# bai1.net
KiCad netlist of a schematic drawn in Altium Designer
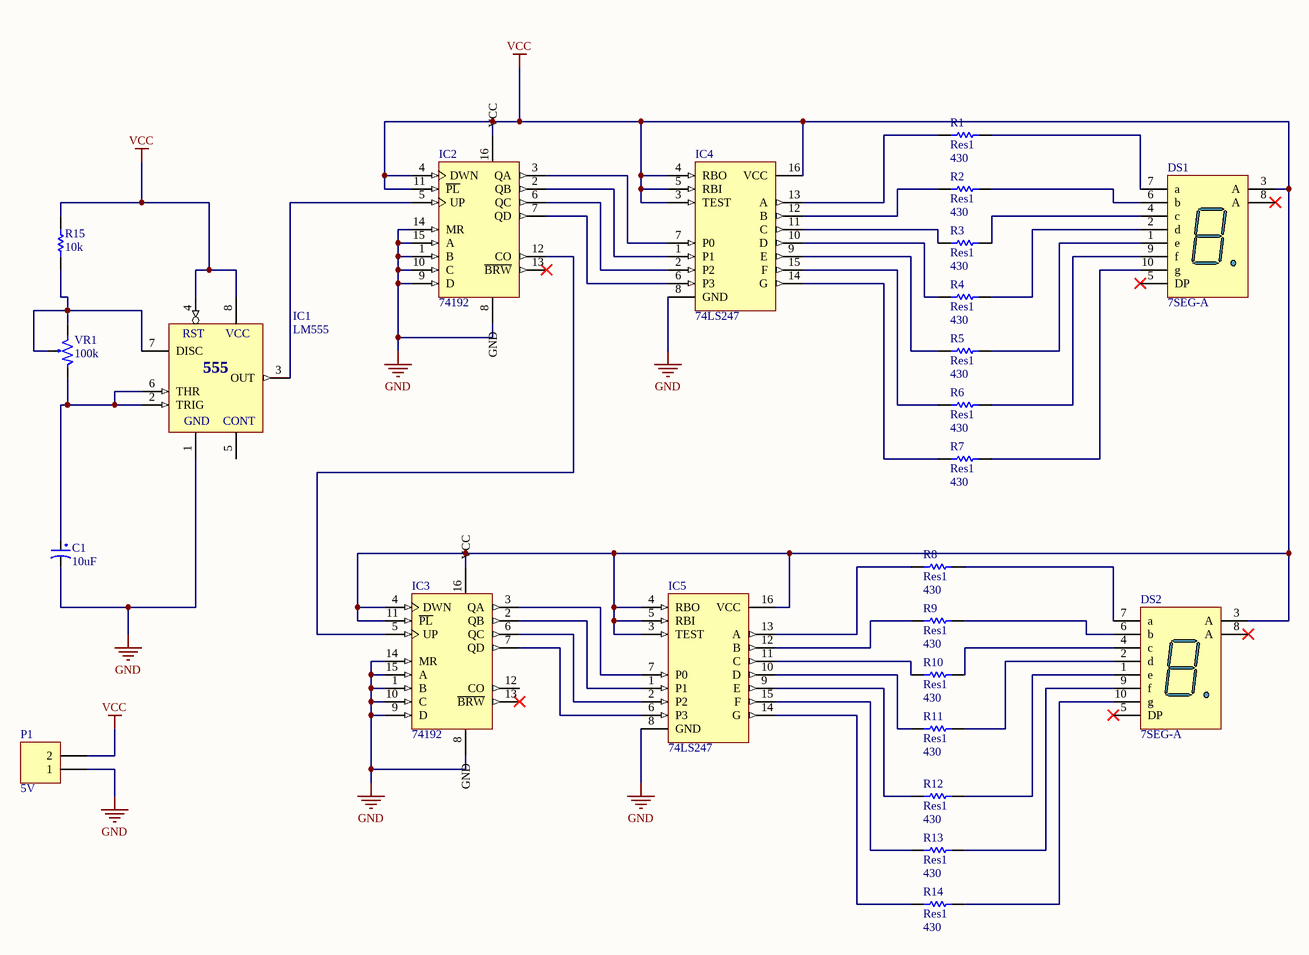
[diagram p0: bai1.SchDoc]

(export (version "E")
  (design (tool "Eeschema 10.0.6"))
  (components
    (comp (ref "C1")
      (value "10uF")
      (footprint "CP1/2")
      (description "Cap P  0,1uF < 22uF , 16 - 50V")
      (libsource (lib "syhaunguyen") (part "CP1"))
    )
    (comp (ref "DS1")
      (value "7SEG-A")
      (footprint "LED7SEG")
      (description "14.2 mm General Purpose Blue 7-Segment Display: CA, RH DP, Gray Surface")
      (fields (field (name "PUBLISHER") "Altium Limited"))
      (libsource (lib "Cty1") (part "LED7SEG-A"))
    )
    (comp (ref "DS2")
      (value "7SEG-A")
      (footprint "LED7SEG")
      (description "14.2 mm General Purpose Blue 7-Segment Display: CA, RH DP, Gray Surface")
      (fields (field (name "PUBLISHER") "Altium Limited"))
      (libsource (lib "Cty1") (part "LED7SEG-A"))
    )
    (comp (ref "IC1")
      (value "LM555")
      (footprint "VioletofSun:DIP8/W0.3")
      (description "Timer")
      (libsource (lib "VioletofSun") (part "LM555"))
    )
    (comp (ref "IC2")
      (value "74192")
      (footprint "DIP16/W0.3")
      (description "Synchronous 4-Bit Up/Down Counter")
      (fields (field (name "COPYRIGHT BY") "VanDungEvn@Gmail.com"))
      (libsource (lib "VioletofSun") (part "74193"))
    )
    (comp (ref "IC3")
      (value "74192")
      (footprint "DIP16/W0.3")
      (description "Synchronous 4-Bit Up/Down Counter")
      (fields (field (name "COPYRIGHT BY") "VanDungEvn@Gmail.com"))
      (libsource (lib "VioletofSun") (part "74193"))
    )
    (comp (ref "IC4")
      (value "74LS247")
      (footprint "DIP16")
      (fields (field (name "COPYRIGHT BY") "VanDungEvn@Gmail.com"))
      (libsource (lib "My Library") (part "74247"))
    )
    (comp (ref "IC5")
      (value "74LS247")
      (footprint "DIP16")
      (fields (field (name "COPYRIGHT BY") "VanDungEvn@Gmail.com"))
      (libsource (lib "My Library") (part "74247"))
    )
    (comp (ref "P1")
      (value "5V")
      (footprint "HDR1X2")
      (description "Header, 2-Pin")
      (fields (field (name "PUBLISHER") "Altium Limited"))
      (libsource (lib "Miscellaneous Connectors") (part "Header 2"))
    )
    (comp (ref "R1")
      (value "Res1")
      (footprint "AXIAL-0.3")
      (description "Resistor")
      (fields (field (name "ALTIUM_VALUE") "430") (field (name "PUBLISHER") "Altium Limited"))
      (libsource (lib "Miscellaneous Devices") (part "Res1"))
    )
    (comp (ref "R2")
      (value "Res1")
      (footprint "AXIAL-0.3")
      (description "Resistor")
      (fields (field (name "ALTIUM_VALUE") "430") (field (name "PUBLISHER") "Altium Limited"))
      (libsource (lib "Miscellaneous Devices") (part "Res1"))
    )
    (comp (ref "R3")
      (value "Res1")
      (footprint "AXIAL-0.3")
      (description "Resistor")
      (fields (field (name "ALTIUM_VALUE") "430") (field (name "PUBLISHER") "Altium Limited"))
      (libsource (lib "Miscellaneous Devices") (part "Res1"))
    )
    (comp (ref "R4")
      (value "Res1")
      (footprint "AXIAL-0.3")
      (description "Resistor")
      (fields (field (name "ALTIUM_VALUE") "430") (field (name "PUBLISHER") "Altium Limited"))
      (libsource (lib "Miscellaneous Devices") (part "Res1"))
    )
    (comp (ref "R5")
      (value "Res1")
      (footprint "AXIAL-0.3")
      (description "Resistor")
      (fields (field (name "ALTIUM_VALUE") "430") (field (name "PUBLISHER") "Altium Limited"))
      (libsource (lib "Miscellaneous Devices") (part "Res1"))
    )
    (comp (ref "R6")
      (value "Res1")
      (footprint "AXIAL-0.3")
      (description "Resistor")
      (fields (field (name "ALTIUM_VALUE") "430") (field (name "PUBLISHER") "Altium Limited"))
      (libsource (lib "Miscellaneous Devices") (part "Res1"))
    )
    (comp (ref "R7")
      (value "Res1")
      (footprint "AXIAL-0.3")
      (description "Resistor")
      (fields (field (name "ALTIUM_VALUE") "430") (field (name "PUBLISHER") "Altium Limited"))
      (libsource (lib "Miscellaneous Devices") (part "Res1"))
    )
    (comp (ref "R8")
      (value "Res1")
      (footprint "AXIAL-0.3")
      (description "Resistor")
      (fields (field (name "ALTIUM_VALUE") "430") (field (name "PUBLISHER") "Altium Limited"))
      (libsource (lib "Miscellaneous Devices") (part "Res1"))
    )
    (comp (ref "R9")
      (value "Res1")
      (footprint "AXIAL-0.3")
      (description "Resistor")
      (fields (field (name "ALTIUM_VALUE") "430") (field (name "PUBLISHER") "Altium Limited"))
      (libsource (lib "Miscellaneous Devices") (part "Res1"))
    )
    (comp (ref "R10")
      (value "Res1")
      (footprint "AXIAL-0.3")
      (description "Resistor")
      (fields (field (name "ALTIUM_VALUE") "430") (field (name "PUBLISHER") "Altium Limited"))
      (libsource (lib "Miscellaneous Devices") (part "Res1"))
    )
    (comp (ref "R11")
      (value "Res1")
      (footprint "AXIAL-0.3")
      (description "Resistor")
      (fields (field (name "ALTIUM_VALUE") "430") (field (name "PUBLISHER") "Altium Limited"))
      (libsource (lib "Miscellaneous Devices") (part "Res1"))
    )
    (comp (ref "R12")
      (value "Res1")
      (footprint "AXIAL-0.3")
      (description "Resistor")
      (fields (field (name "ALTIUM_VALUE") "430") (field (name "PUBLISHER") "Altium Limited"))
      (libsource (lib "Miscellaneous Devices") (part "Res1"))
    )
    (comp (ref "R13")
      (value "Res1")
      (footprint "AXIAL-0.3")
      (description "Resistor")
      (fields (field (name "ALTIUM_VALUE") "430") (field (name "PUBLISHER") "Altium Limited"))
      (libsource (lib "Miscellaneous Devices") (part "Res1"))
    )
    (comp (ref "R14")
      (value "Res1")
      (footprint "AXIAL-0.3")
      (description "Resistor")
      (fields (field (name "ALTIUM_VALUE") "430") (field (name "PUBLISHER") "Altium Limited"))
      (libsource (lib "Miscellaneous Devices") (part "Res1"))
    )
    (comp (ref "R15")
      (value "10k")
      (footprint "R1/4W")
      (description "Resistor")
      (fields
        (field (name "MANUFACTURER") "Generic Components")
        (field (name "Comment") "Res1")
        (field (name "PUBLISHER") "Altium Hobart Technology Centre")
      )
      (libsource (lib "thuvien3D") (part "Res1_1"))
    )
    (comp (ref "VR1")
      (value "100k")
      (footprint "VR")
      (description "Var Resistor")
      (libsource (lib "syhaunguyen") (part "VR1"))
    )
  )
  (nets
    (net (code "1") (name "GND") (class "Default")
      (node (ref "C1") (pin "2") (pinfunction "2_2") (pintype "passive"))
      (node (ref "IC1") (pin "1") (pinfunction "GND_1") (pintype "power_in"))
      (node (ref "IC2") (pin "1") (pinfunction "B_1") (pintype "input"))
      (node (ref "IC2") (pin "10") (pinfunction "C_10") (pintype "input"))
      (node (ref "IC2") (pin "14") (pinfunction "MR_14") (pintype "input"))
      (node (ref "IC2") (pin "15") (pinfunction "A_15") (pintype "input"))
      (node (ref "IC2") (pin "9") (pinfunction "D_9") (pintype "input"))
      (node (ref "IC3") (pin "1") (pinfunction "B_1") (pintype "input"))
      (node (ref "IC3") (pin "10") (pinfunction "C_10") (pintype "input"))
      (node (ref "IC3") (pin "14") (pinfunction "MR_14") (pintype "input"))
      (node (ref "IC3") (pin "15") (pinfunction "A_15") (pintype "input"))
      (node (ref "IC3") (pin "9") (pinfunction "D_9") (pintype "input"))
      (node (ref "IC4") (pin "8") (pinfunction "GND_8") (pintype "power_in"))
      (node (ref "IC5") (pin "8") (pinfunction "GND_8") (pintype "power_in"))
      (node (ref "P1") (pin "1") (pinfunction "1_1") (pintype "passive"))
    )
    (net (code "2") (name "Net-(DS1-a)") (class "Default")
      (node (ref "DS1") (pin "7") (pinfunction "a_7") (pintype "passive"))
      (node (ref "R1") (pin "2") (pinfunction "2_2") (pintype "passive"))
    )
    (net (code "3") (name "Net-(DS1-b)") (class "Default")
      (node (ref "DS1") (pin "6") (pinfunction "b_6") (pintype "passive"))
      (node (ref "R2") (pin "2") (pinfunction "2_2") (pintype "passive"))
    )
    (net (code "4") (name "Net-(DS1-c)") (class "Default")
      (node (ref "DS1") (pin "4") (pinfunction "c_4") (pintype "passive"))
      (node (ref "R3") (pin "2") (pinfunction "2_2") (pintype "passive"))
    )
    (net (code "5") (name "Net-(DS1-d)") (class "Default")
      (node (ref "DS1") (pin "2") (pinfunction "d_2") (pintype "passive"))
      (node (ref "R4") (pin "2") (pinfunction "2_2") (pintype "passive"))
    )
    (net (code "6") (name "Net-(DS1-e)") (class "Default")
      (node (ref "DS1") (pin "1") (pinfunction "e_1") (pintype "passive"))
      (node (ref "R5") (pin "2") (pinfunction "2_2") (pintype "passive"))
    )
    (net (code "7") (name "Net-(DS1-f)") (class "Default")
      (node (ref "DS1") (pin "9") (pinfunction "f_9") (pintype "passive"))
      (node (ref "R6") (pin "2") (pinfunction "2_2") (pintype "passive"))
    )
    (net (code "8") (name "Net-(DS1-g)") (class "Default")
      (node (ref "DS1") (pin "10") (pinfunction "g_10") (pintype "passive"))
      (node (ref "R7") (pin "2") (pinfunction "2_2") (pintype "passive"))
    )
    (net (code "9") (name "Net-(DS2-a)") (class "Default")
      (node (ref "DS2") (pin "7") (pinfunction "a_7") (pintype "passive"))
      (node (ref "R8") (pin "2") (pinfunction "2_2") (pintype "passive"))
    )
    (net (code "10") (name "Net-(DS2-b)") (class "Default")
      (node (ref "DS2") (pin "6") (pinfunction "b_6") (pintype "passive"))
      (node (ref "R9") (pin "2") (pinfunction "2_2") (pintype "passive"))
    )
    (net (code "11") (name "Net-(DS2-c)") (class "Default")
      (node (ref "DS2") (pin "4") (pinfunction "c_4") (pintype "passive"))
      (node (ref "R10") (pin "2") (pinfunction "2_2") (pintype "passive"))
    )
    (net (code "12") (name "Net-(DS2-d)") (class "Default")
      (node (ref "DS2") (pin "2") (pinfunction "d_2") (pintype "passive"))
      (node (ref "R11") (pin "2") (pinfunction "2_2") (pintype "passive"))
    )
    (net (code "13") (name "Net-(DS2-e)") (class "Default")
      (node (ref "DS2") (pin "1") (pinfunction "e_1") (pintype "passive"))
      (node (ref "R12") (pin "2") (pinfunction "2_2") (pintype "passive"))
    )
    (net (code "14") (name "Net-(DS2-f)") (class "Default")
      (node (ref "DS2") (pin "9") (pinfunction "f_9") (pintype "passive"))
      (node (ref "R13") (pin "2") (pinfunction "2_2") (pintype "passive"))
    )
    (net (code "15") (name "Net-(DS2-g)") (class "Default")
      (node (ref "DS2") (pin "10") (pinfunction "g_10") (pintype "passive"))
      (node (ref "R14") (pin "2") (pinfunction "2_2") (pintype "passive"))
    )
    (net (code "16") (name "Net-(IC1-DISC)") (class "Default")
      (node (ref "IC1") (pin "7") (pinfunction "DISC_7") (pintype "open_collector"))
      (node (ref "R15") (pin "1") (pinfunction "1_1") (pintype "passive"))
      (node (ref "VR1") (pin "2") (pinfunction "2_2") (pintype "passive"))
      (node (ref "VR1") (pin "3") (pinfunction "3_3") (pintype "passive"))
    )
    (net (code "17") (name "Net-(IC1-OUT)") (class "Default")
      (node (ref "IC1") (pin "3") (pinfunction "OUT_3") (pintype "output"))
      (node (ref "IC2") (pin "5") (pinfunction "UP_5") (pintype "input"))
    )
    (net (code "18") (name "Net-(IC1-THR)") (class "Default")
      (node (ref "C1") (pin "1") (pinfunction "1_1") (pintype "passive"))
      (node (ref "IC1") (pin "2") (pinfunction "TRIG_2") (pintype "input"))
      (node (ref "IC1") (pin "6") (pinfunction "THR_6") (pintype "input"))
      (node (ref "VR1") (pin "1") (pinfunction "1_1") (pintype "passive"))
    )
    (net (code "19") (name "Net-(IC2-CO)") (class "Default")
      (node (ref "IC2") (pin "12") (pinfunction "CO_12") (pintype "output"))
      (node (ref "IC3") (pin "5") (pinfunction "UP_5") (pintype "input"))
    )
    (net (code "20") (name "Net-(IC2-QA)") (class "Default")
      (node (ref "IC2") (pin "3") (pinfunction "QA_3") (pintype "output"))
      (node (ref "IC4") (pin "7") (pinfunction "P0_7") (pintype "input"))
    )
    (net (code "21") (name "Net-(IC2-QB)") (class "Default")
      (node (ref "IC2") (pin "2") (pinfunction "QB_2") (pintype "output"))
      (node (ref "IC4") (pin "1") (pinfunction "P1_1") (pintype "input"))
    )
    (net (code "22") (name "Net-(IC2-QC)") (class "Default")
      (node (ref "IC2") (pin "6") (pinfunction "QC_6") (pintype "output"))
      (node (ref "IC4") (pin "2") (pinfunction "P2_2") (pintype "input"))
    )
    (net (code "23") (name "Net-(IC2-QD)") (class "Default")
      (node (ref "IC2") (pin "7") (pinfunction "QD_7") (pintype "output"))
      (node (ref "IC4") (pin "6") (pinfunction "P3_6") (pintype "input"))
    )
    (net (code "24") (name "Net-(IC3-QA)") (class "Default")
      (node (ref "IC3") (pin "3") (pinfunction "QA_3") (pintype "output"))
      (node (ref "IC5") (pin "7") (pinfunction "P0_7") (pintype "input"))
    )
    (net (code "25") (name "Net-(IC3-QB)") (class "Default")
      (node (ref "IC3") (pin "2") (pinfunction "QB_2") (pintype "output"))
      (node (ref "IC5") (pin "1") (pinfunction "P1_1") (pintype "input"))
    )
    (net (code "26") (name "Net-(IC3-QC)") (class "Default")
      (node (ref "IC3") (pin "6") (pinfunction "QC_6") (pintype "output"))
      (node (ref "IC5") (pin "2") (pinfunction "P2_2") (pintype "input"))
    )
    (net (code "27") (name "Net-(IC3-QD)") (class "Default")
      (node (ref "IC3") (pin "7") (pinfunction "QD_7") (pintype "output"))
      (node (ref "IC5") (pin "6") (pinfunction "P3_6") (pintype "input"))
    )
    (net (code "28") (name "Net-(IC4-A)") (class "Default")
      (node (ref "IC4") (pin "13") (pinfunction "A_13") (pintype "output"))
      (node (ref "R1") (pin "1") (pinfunction "1_1") (pintype "passive"))
    )
    (net (code "29") (name "Net-(IC4-B)") (class "Default")
      (node (ref "IC4") (pin "12") (pinfunction "B_12") (pintype "output"))
      (node (ref "R2") (pin "1") (pinfunction "1_1") (pintype "passive"))
    )
    (net (code "30") (name "Net-(IC4-C)") (class "Default")
      (node (ref "IC4") (pin "11") (pinfunction "C_11") (pintype "output"))
      (node (ref "R3") (pin "1") (pinfunction "1_1") (pintype "passive"))
    )
    (net (code "31") (name "Net-(IC4-D)") (class "Default")
      (node (ref "IC4") (pin "10") (pinfunction "D_10") (pintype "output"))
      (node (ref "R4") (pin "1") (pinfunction "1_1") (pintype "passive"))
    )
    (net (code "32") (name "Net-(IC4-E)") (class "Default")
      (node (ref "IC4") (pin "9") (pinfunction "E_9") (pintype "output"))
      (node (ref "R5") (pin "1") (pinfunction "1_1") (pintype "passive"))
    )
    (net (code "33") (name "Net-(IC4-F)") (class "Default")
      (node (ref "IC4") (pin "15") (pinfunction "F_15") (pintype "output"))
      (node (ref "R6") (pin "1") (pinfunction "1_1") (pintype "passive"))
    )
    (net (code "34") (name "Net-(IC4-G)") (class "Default")
      (node (ref "IC4") (pin "14") (pinfunction "G_14") (pintype "output"))
      (node (ref "R7") (pin "1") (pinfunction "1_1") (pintype "passive"))
    )
    (net (code "35") (name "Net-(IC5-A)") (class "Default")
      (node (ref "IC5") (pin "13") (pinfunction "A_13") (pintype "output"))
      (node (ref "R8") (pin "1") (pinfunction "1_1") (pintype "passive"))
    )
    (net (code "36") (name "Net-(IC5-B)") (class "Default")
      (node (ref "IC5") (pin "12") (pinfunction "B_12") (pintype "output"))
      (node (ref "R9") (pin "1") (pinfunction "1_1") (pintype "passive"))
    )
    (net (code "37") (name "Net-(IC5-C)") (class "Default")
      (node (ref "IC5") (pin "11") (pinfunction "C_11") (pintype "output"))
      (node (ref "R10") (pin "1") (pinfunction "1_1") (pintype "passive"))
    )
    (net (code "38") (name "Net-(IC5-D)") (class "Default")
      (node (ref "IC5") (pin "10") (pinfunction "D_10") (pintype "output"))
      (node (ref "R11") (pin "1") (pinfunction "1_1") (pintype "passive"))
    )
    (net (code "39") (name "Net-(IC5-E)") (class "Default")
      (node (ref "IC5") (pin "9") (pinfunction "E_9") (pintype "output"))
      (node (ref "R12") (pin "1") (pinfunction "1_1") (pintype "passive"))
    )
    (net (code "40") (name "Net-(IC5-F)") (class "Default")
      (node (ref "IC5") (pin "15") (pinfunction "F_15") (pintype "output"))
      (node (ref "R13") (pin "1") (pinfunction "1_1") (pintype "passive"))
    )
    (net (code "41") (name "Net-(IC5-G)") (class "Default")
      (node (ref "IC5") (pin "14") (pinfunction "G_14") (pintype "output"))
      (node (ref "R14") (pin "1") (pinfunction "1_1") (pintype "passive"))
    )
    (net (code "42") (name "VCC") (class "Default")
      (node (ref "DS1") (pin "3") (pinfunction "A_3") (pintype "passive"))
      (node (ref "DS2") (pin "3") (pinfunction "A_3") (pintype "passive"))
      (node (ref "IC1") (pin "4") (pinfunction "RST_4") (pintype "input"))
      (node (ref "IC1") (pin "8") (pinfunction "VCC_8") (pintype "power_in"))
      (node (ref "IC2") (pin "11") (pinfunction "~{PL}_11") (pintype "input"))
      (node (ref "IC2") (pin "4") (pinfunction "DWN_4") (pintype "input"))
      (node (ref "IC3") (pin "11") (pinfunction "~{PL}_11") (pintype "input"))
      (node (ref "IC3") (pin "4") (pinfunction "DWN_4") (pintype "input"))
      (node (ref "IC4") (pin "16") (pinfunction "VCC_16") (pintype "power_in"))
      (node (ref "IC4") (pin "3") (pinfunction "TEST_3") (pintype "input"))
      (node (ref "IC4") (pin "4") (pinfunction "RBO_4") (pintype "input"))
      (node (ref "IC4") (pin "5") (pinfunction "RBI_5") (pintype "input"))
      (node (ref "IC5") (pin "16") (pinfunction "VCC_16") (pintype "power_in"))
      (node (ref "IC5") (pin "3") (pinfunction "TEST_3") (pintype "input"))
      (node (ref "IC5") (pin "4") (pinfunction "RBO_4") (pintype "input"))
      (node (ref "IC5") (pin "5") (pinfunction "RBI_5") (pintype "input"))
      (node (ref "P1") (pin "2") (pinfunction "2_2") (pintype "passive"))
      (node (ref "R15") (pin "2") (pinfunction "2_2") (pintype "passive"))
    )
    (net (code "43") (name "unconnected-(DS1-A-Pad8)") (class "Default")
      (node (ref "DS1") (pin "8") (pinfunction "A_8") (pintype "passive+no_connect"))
    )
    (net (code "44") (name "unconnected-(DS1-DP-Pad5)") (class "Default")
      (node (ref "DS1") (pin "5") (pinfunction "DP_5") (pintype "passive+no_connect"))
    )
    (net (code "45") (name "unconnected-(DS2-A-Pad8)") (class "Default")
      (node (ref "DS2") (pin "8") (pinfunction "A_8") (pintype "passive+no_connect"))
    )
    (net (code "46") (name "unconnected-(DS2-DP-Pad5)") (class "Default")
      (node (ref "DS2") (pin "5") (pinfunction "DP_5") (pintype "passive+no_connect"))
    )
    (net (code "47") (name "unconnected-(IC1-CONT-Pad5)") (class "Default")
      (node (ref "IC1") (pin "5") (pinfunction "CONT_5") (pintype "passive"))
    )
    (net (code "48") (name "unconnected-(IC2-GND-Pad8)") (class "Default")
      (node (ref "IC2") (pin "8") (pinfunction "GND_8") (pintype "power_in"))
    )
    (net (code "49") (name "unconnected-(IC2-VCC-Pad16)") (class "Default")
      (node (ref "IC2") (pin "16") (pinfunction "VCC_16") (pintype "power_in"))
    )
    (net (code "50") (name "unconnected-(IC2-~{BRW}-Pad13)") (class "Default")
      (node (ref "IC2") (pin "13") (pinfunction "~{BRW}_13") (pintype "output+no_connect"))
    )
    (net (code "51") (name "unconnected-(IC3-CO-Pad12)") (class "Default")
      (node (ref "IC3") (pin "12") (pinfunction "CO_12") (pintype "output"))
    )
    (net (code "52") (name "unconnected-(IC3-GND-Pad8)") (class "Default")
      (node (ref "IC3") (pin "8") (pinfunction "GND_8") (pintype "power_in"))
    )
    (net (code "53") (name "unconnected-(IC3-VCC-Pad16)") (class "Default")
      (node (ref "IC3") (pin "16") (pinfunction "VCC_16") (pintype "power_in"))
    )
    (net (code "54") (name "unconnected-(IC3-~{BRW}-Pad13)") (class "Default")
      (node (ref "IC3") (pin "13") (pinfunction "~{BRW}_13") (pintype "output+no_connect"))
    )
  )
)
